# Level_Shifter.net
KiCad netlist of a schematic drawn in Altium Designer
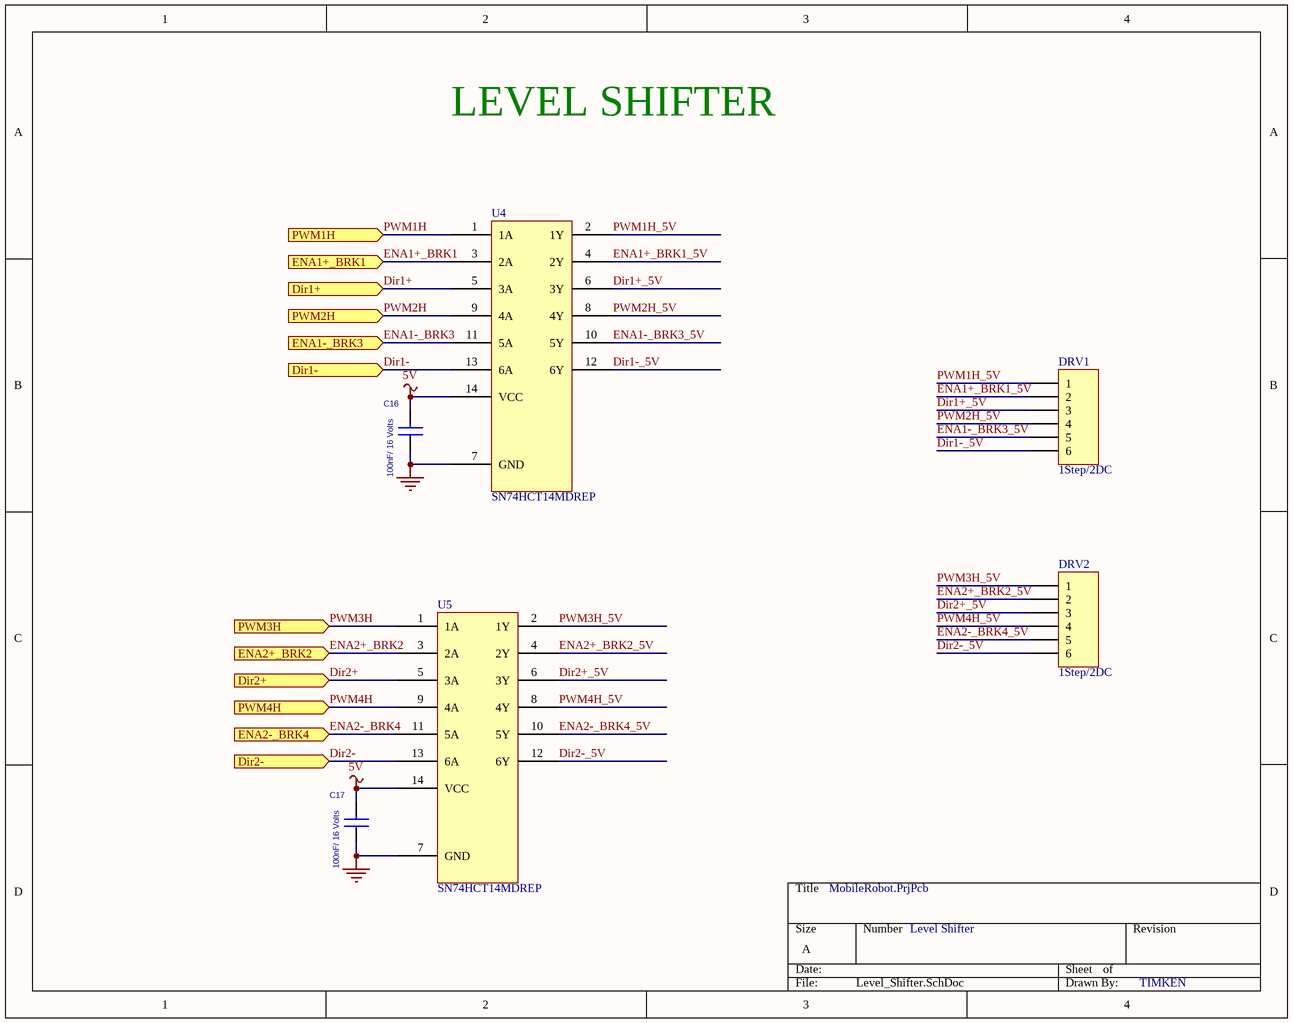
[diagram p0: Level_Shifter.SchDoc]

(export (version "E")
  (design (tool "Eeschema 10.0.6"))
  (components
    (comp (ref "C16")
      (value "100nF/ 16 Volts")
      (footprint "CAP_CERAMIC")
      (libsource (lib "combined_cart_schematic_lib") (part "CAP NP"))
    )
    (comp (ref "C17")
      (value "100nF/ 16 Volts")
      (footprint "CAP_CERAMIC")
      (libsource (lib "combined_cart_schematic_lib") (part "CAP NP"))
    )
    (comp (ref "DRV1")
      (value "1Step/2DC")
      (footprint "1x6_single")
      (description "Header, 6-Pin")
      (fields (field (name "PUBLISHER") "Altium Limited"))
      (libsource (lib "combined_cart_schematic_lib") (part "Header 6"))
    )
    (comp (ref "DRV2")
      (value "1Step/2DC")
      (footprint "1x6_single")
      (description "Header, 6-Pin")
      (fields (field (name "PUBLISHER") "Altium Limited"))
      (libsource (lib "combined_cart_schematic_lib") (part "Header 6"))
    )
    (comp (ref "U4")
      (value "SN74HCT14MDREP")
      (footprint "SN74HCT14MDREP")
      (libsource (lib "combined_cart_schematic_lib") (part "74HC153D"))
    )
    (comp (ref "U5")
      (value "SN74HCT14MDREP")
      (footprint "SN74HCT14MDREP")
      (libsource (lib "combined_cart_schematic_lib") (part "74HC153D"))
    )
  )
  (nets
    (net (code "1") (name "/Dir1+") (class "Default")
      (node (ref "U4") (pin "5") (pinfunction "3A_5") (pintype "passive"))
    )
    (net (code "2") (name "/Dir1+_5V") (class "Default")
      (node (ref "DRV1") (pin "3") (pinfunction "3_3") (pintype "passive"))
      (node (ref "U4") (pin "6") (pinfunction "3Y_6") (pintype "passive"))
    )
    (net (code "3") (name "/Dir1-") (class "Default")
      (node (ref "U4") (pin "13") (pinfunction "6A_13") (pintype "passive"))
    )
    (net (code "4") (name "/Dir1-_5V") (class "Default")
      (node (ref "DRV1") (pin "6") (pinfunction "6_6") (pintype "passive"))
      (node (ref "U4") (pin "12") (pinfunction "6Y_12") (pintype "passive"))
    )
    (net (code "5") (name "/Dir2+") (class "Default")
      (node (ref "U5") (pin "5") (pinfunction "3A_5") (pintype "passive"))
    )
    (net (code "6") (name "/Dir2+_5V") (class "Default")
      (node (ref "DRV2") (pin "3") (pinfunction "3_3") (pintype "passive"))
      (node (ref "U5") (pin "6") (pinfunction "3Y_6") (pintype "passive"))
    )
    (net (code "7") (name "/Dir2-") (class "Default")
      (node (ref "U5") (pin "13") (pinfunction "6A_13") (pintype "passive"))
    )
    (net (code "8") (name "/Dir2-_5V") (class "Default")
      (node (ref "DRV2") (pin "6") (pinfunction "6_6") (pintype "passive"))
      (node (ref "U5") (pin "12") (pinfunction "6Y_12") (pintype "passive"))
    )
    (net (code "9") (name "/ENA1+_BRK1") (class "Default")
      (node (ref "U4") (pin "3") (pinfunction "2A_3") (pintype "passive"))
    )
    (net (code "10") (name "/ENA1+_BRK1_5V") (class "Default")
      (node (ref "DRV1") (pin "2") (pinfunction "2_2") (pintype "passive"))
      (node (ref "U4") (pin "4") (pinfunction "2Y_4") (pintype "passive"))
    )
    (net (code "11") (name "/ENA1-_BRK3") (class "Default")
      (node (ref "U4") (pin "11") (pinfunction "5A_11") (pintype "passive"))
    )
    (net (code "12") (name "/ENA1-_BRK3_5V") (class "Default")
      (node (ref "DRV1") (pin "5") (pinfunction "5_5") (pintype "passive"))
      (node (ref "U4") (pin "10") (pinfunction "5Y_10") (pintype "passive"))
    )
    (net (code "13") (name "/ENA2+_BRK2") (class "Default")
      (node (ref "U5") (pin "3") (pinfunction "2A_3") (pintype "passive"))
    )
    (net (code "14") (name "/ENA2+_BRK2_5V") (class "Default")
      (node (ref "DRV2") (pin "2") (pinfunction "2_2") (pintype "passive"))
      (node (ref "U5") (pin "4") (pinfunction "2Y_4") (pintype "passive"))
    )
    (net (code "15") (name "/ENA2-_BRK4") (class "Default")
      (node (ref "U5") (pin "11") (pinfunction "5A_11") (pintype "passive"))
    )
    (net (code "16") (name "/ENA2-_BRK4_5V") (class "Default")
      (node (ref "DRV2") (pin "5") (pinfunction "5_5") (pintype "passive"))
      (node (ref "U5") (pin "10") (pinfunction "5Y_10") (pintype "passive"))
    )
    (net (code "17") (name "/PWM1H") (class "Default")
      (node (ref "U4") (pin "1") (pinfunction "1A_1") (pintype "passive"))
    )
    (net (code "18") (name "/PWM1H_5V") (class "Default")
      (node (ref "DRV1") (pin "1") (pinfunction "1_1") (pintype "passive"))
      (node (ref "U4") (pin "2") (pinfunction "1Y_2") (pintype "passive"))
    )
    (net (code "19") (name "/PWM2H") (class "Default")
      (node (ref "U4") (pin "9") (pinfunction "4A_9") (pintype "passive"))
    )
    (net (code "20") (name "/PWM2H_5V") (class "Default")
      (node (ref "DRV1") (pin "4") (pinfunction "4_4") (pintype "passive"))
      (node (ref "U4") (pin "8") (pinfunction "4Y_8") (pintype "passive"))
    )
    (net (code "21") (name "/PWM3H") (class "Default")
      (node (ref "U5") (pin "1") (pinfunction "1A_1") (pintype "passive"))
    )
    (net (code "22") (name "/PWM3H_5V") (class "Default")
      (node (ref "DRV2") (pin "1") (pinfunction "1_1") (pintype "passive"))
      (node (ref "U5") (pin "2") (pinfunction "1Y_2") (pintype "passive"))
    )
    (net (code "23") (name "/PWM4H") (class "Default")
      (node (ref "U5") (pin "9") (pinfunction "4A_9") (pintype "passive"))
    )
    (net (code "24") (name "/PWM4H_5V") (class "Default")
      (node (ref "DRV2") (pin "4") (pinfunction "4_4") (pintype "passive"))
      (node (ref "U5") (pin "8") (pinfunction "4Y_8") (pintype "passive"))
    )
    (net (code "25") (name "5V") (class "Default")
      (node (ref "C16") (pin "2") (pinfunction "2_2") (pintype "passive"))
      (node (ref "C17") (pin "2") (pinfunction "2_2") (pintype "passive"))
      (node (ref "U4") (pin "14") (pinfunction "VCC_14") (pintype "passive"))
      (node (ref "U5") (pin "14") (pinfunction "VCC_14") (pintype "passive"))
    )
    (net (code "26") (name "GND_POWER") (class "Default")
      (node (ref "C16") (pin "1") (pinfunction "1_1") (pintype "passive"))
      (node (ref "C17") (pin "1") (pinfunction "1_1") (pintype "passive"))
      (node (ref "U4") (pin "7") (pinfunction "GND_7") (pintype "passive"))
      (node (ref "U5") (pin "7") (pinfunction "GND_7") (pintype "passive"))
    )
  )
)
